# Cell_Terminal_LPF.net
KiCad netlist of a schematic drawn in Altium Designer
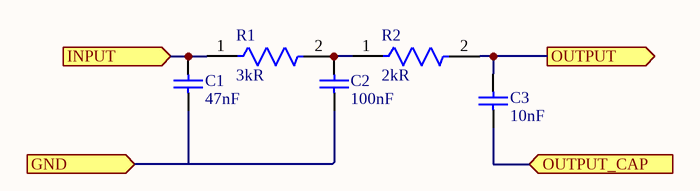
[diagram p0: Cell Terminal LPF.SchDoc]

(export (version "E")
  (design (tool "Eeschema 10.0.6"))
  (components
    (comp (ref "C1")
      (value "47nF")
      (footprint "WCAP-CSGP_0402_L1W0.5H0.5")
      (description "WCAP-CSGP Multilayer Ceramic Chip Capacitor, General Purpose, size 0402, X7R, 47nF, 50VDC")
      (fields
        (field (name "MANUFACTURER PART NUMBER") "885012205092")
        (field (name "MANUFACTURER") "Wurth Elektronik")
      )
      (libsource (lib "Green Team Twente") (part "885012209047R"))
    )
    (comp (ref "C2")
      (value "100nF")
      (footprint "WCAP-CSGP_0402_L1W0.5H0.5")
      (description "WCAP-CSGP Multilayer Ceramic Chip Capacitor, General Purpose, size 0402, X7R, 100nF, 50VDC")
      (fields
        (field (name "MANUFACTURER PART NUMBER") "885012205092")
        (field (name "MANUFACTURER") "Wurth Elektronik")
      )
      (libsource (lib "Green Team Twente") (part "885012209047R"))
    )
    (comp (ref "C3")
      (value "10nF")
      (footprint "WCAP-CSGP_0402_L1W0.5H0.5")
      (description "WCAP-CSGP Multilayer Ceramic Chip Capacitor, General Purpose, size 0402, X7R, 10nF, 50VDC")
      (fields
        (field (name "MANUFACTURER PART NUMBER") "885012205092")
        (field (name "MANUFACTURER") "Wurth Elektronik")
      )
      (libsource (lib "Green Team Twente") (part "885012209047R"))
    )
    (comp (ref "R1")
      (value "3kR 0402 0.1%")
      (footprint "FP-RT0402-0_35-MFG")
      (description "RES SMD 3K OHM 0.1% 1/16W 0402")
      (fields (field (name "RESISTANCE") "3kR") (field (name "TOLERANCE") "0.1%"))
      (libsource (lib "Altium Content Vault") (part "1029c3af85768c4190bb7ad29bc67b5"))
    )
    (comp (ref "R2")
      (value "2kR 0402 0.1%")
      (footprint "FP-RT0402-0_35-MFG")
      (description "RES SMD 2K OHM 0.1% 1/16W 0402")
      (fields (field (name "RESISTANCE") "2kR") (field (name "TOLERANCE") "0.1%"))
      (libsource (lib "Altium Content Vault") (part "1029c3af85768c4190bb7ad29bc67b5"))
    )
  )
  (nets
    (net (code "1") (name "/GND") (class "Default")
      (node (ref "C1") (pin "1") (pinfunction "1_1") (pintype "passive"))
      (node (ref "C2") (pin "1") (pinfunction "1_1") (pintype "passive"))
    )
    (net (code "2") (name "/INPUT") (class "Default")
      (node (ref "C1") (pin "2") (pinfunction "2_2") (pintype "passive"))
      (node (ref "R1") (pin "1") (pinfunction "1_1") (pintype "passive"))
    )
    (net (code "3") (name "/OUTPUT") (class "Default")
      (node (ref "C3") (pin "2") (pinfunction "2_2") (pintype "passive"))
      (node (ref "R2") (pin "2") (pinfunction "2_2") (pintype "passive"))
    )
    (net (code "4") (name "/OUTPUT_CAP") (class "Default")
      (node (ref "C3") (pin "1") (pinfunction "1_1") (pintype "passive"))
    )
    (net (code "5") (name "Net-(C2-Pad2)") (class "Default")
      (node (ref "C2") (pin "2") (pinfunction "2_2") (pintype "passive"))
      (node (ref "R1") (pin "2") (pinfunction "2_2") (pintype "passive"))
      (node (ref "R2") (pin "1") (pinfunction "1_1") (pintype "passive"))
    )
  )
)
